# lora_breakout_36_pin.net
KiCad netlist of a schematic drawn in EAGLE
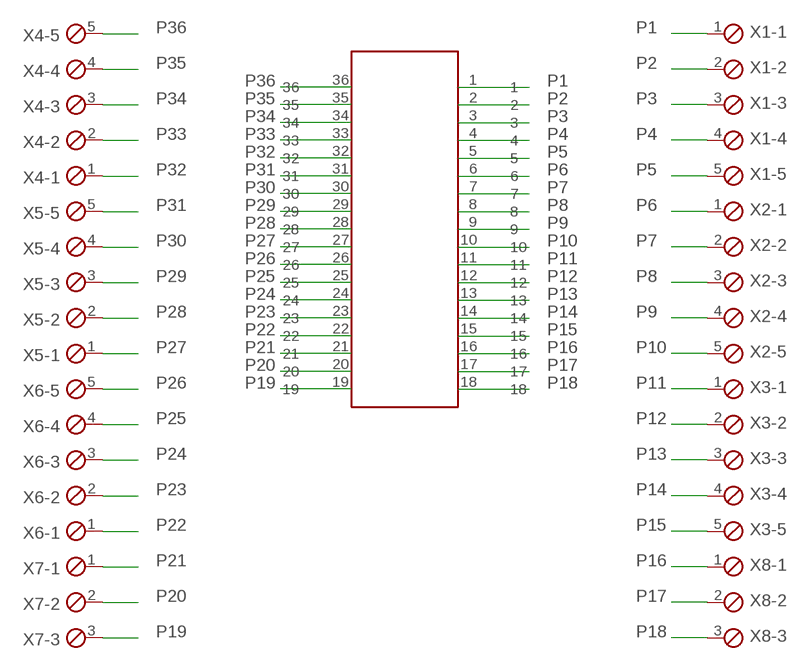
[diagram p0: schematic, sheet 1]

(export (version "E")
  (design (tool "Eeschema 10.0.6"))
  (components
    (comp (ref "U$1")
      (value "HELTECLORA")
      (footprint "eagle-import:HELTECLORA")
      (libsource (lib "eagle-import") (part "HELTECLORA"))
    )
    (comp (ref "X1")
      (value "MPT5")
      (footprint "eagle-import:5POL254")
      (libsource (lib "eagle-import") (part "MPT5"))
    )
    (comp (ref "X2")
      (value "MPT5")
      (footprint "eagle-import:5POL254")
      (libsource (lib "eagle-import") (part "MPT5"))
    )
    (comp (ref "X3")
      (value "MPT5")
      (footprint "eagle-import:5POL254")
      (libsource (lib "eagle-import") (part "MPT5"))
    )
    (comp (ref "X4")
      (value "MPT5")
      (footprint "eagle-import:5POL254")
      (libsource (lib "eagle-import") (part "MPT5"))
    )
    (comp (ref "X5")
      (value "MPT5")
      (footprint "eagle-import:5POL254")
      (libsource (lib "eagle-import") (part "MPT5"))
    )
    (comp (ref "X6")
      (value "MPT5")
      (footprint "eagle-import:5POL254")
      (libsource (lib "eagle-import") (part "MPT5"))
    )
    (comp (ref "X7")
      (value "MPT3")
      (footprint "eagle-import:3POL254")
      (libsource (lib "eagle-import") (part "MPT3"))
    )
    (comp (ref "X8")
      (value "MPT3")
      (footprint "eagle-import:3POL254")
      (libsource (lib "eagle-import") (part "MPT3"))
    )
  )
  (nets
    (net (code "1") (name "/P1") (class "Default")
      (node (ref "U$1") (pin "1") (pinfunction "1_1") (pintype "bidirectional"))
      (node (ref "X1") (pin "1") (pinfunction "1_1") (pintype "passive"))
    )
    (net (code "2") (name "/P2") (class "Default")
      (node (ref "U$1") (pin "2") (pinfunction "2_2") (pintype "bidirectional"))
      (node (ref "X1") (pin "2") (pinfunction "1_2") (pintype "passive"))
    )
    (net (code "3") (name "/P3") (class "Default")
      (node (ref "U$1") (pin "3") (pinfunction "3_3") (pintype "bidirectional"))
      (node (ref "X1") (pin "3") (pinfunction "1_3") (pintype "passive"))
    )
    (net (code "4") (name "/P4") (class "Default")
      (node (ref "U$1") (pin "4") (pinfunction "4_4") (pintype "bidirectional"))
      (node (ref "X1") (pin "4") (pinfunction "1_4") (pintype "passive"))
    )
    (net (code "5") (name "/P5") (class "Default")
      (node (ref "U$1") (pin "5") (pinfunction "5_5") (pintype "bidirectional"))
      (node (ref "X1") (pin "5") (pinfunction "1_5") (pintype "passive"))
    )
    (net (code "6") (name "/P6") (class "Default")
      (node (ref "U$1") (pin "6") (pinfunction "6_6") (pintype "bidirectional"))
      (node (ref "X2") (pin "1") (pinfunction "1_1") (pintype "passive"))
    )
    (net (code "7") (name "/P7") (class "Default")
      (node (ref "U$1") (pin "7") (pinfunction "7_7") (pintype "bidirectional"))
      (node (ref "X2") (pin "2") (pinfunction "1_2") (pintype "passive"))
    )
    (net (code "8") (name "/P8") (class "Default")
      (node (ref "U$1") (pin "8") (pinfunction "8_8") (pintype "bidirectional"))
      (node (ref "X2") (pin "3") (pinfunction "1_3") (pintype "passive"))
    )
    (net (code "9") (name "/P9") (class "Default")
      (node (ref "U$1") (pin "9") (pinfunction "9_9") (pintype "bidirectional"))
      (node (ref "X2") (pin "4") (pinfunction "1_4") (pintype "passive"))
    )
    (net (code "10") (name "/P10") (class "Default")
      (node (ref "U$1") (pin "10") (pinfunction "10_10") (pintype "bidirectional"))
      (node (ref "X2") (pin "5") (pinfunction "1_5") (pintype "passive"))
    )
    (net (code "11") (name "/P11") (class "Default")
      (node (ref "U$1") (pin "11") (pinfunction "11_11") (pintype "bidirectional"))
      (node (ref "X3") (pin "1") (pinfunction "1_1") (pintype "passive"))
    )
    (net (code "12") (name "/P12") (class "Default")
      (node (ref "U$1") (pin "12") (pinfunction "12_12") (pintype "bidirectional"))
      (node (ref "X3") (pin "2") (pinfunction "1_2") (pintype "passive"))
    )
    (net (code "13") (name "/P13") (class "Default")
      (node (ref "U$1") (pin "13") (pinfunction "13_13") (pintype "bidirectional"))
      (node (ref "X3") (pin "3") (pinfunction "1_3") (pintype "passive"))
    )
    (net (code "14") (name "/P14") (class "Default")
      (node (ref "U$1") (pin "14") (pinfunction "14_14") (pintype "bidirectional"))
      (node (ref "X3") (pin "4") (pinfunction "1_4") (pintype "passive"))
    )
    (net (code "15") (name "/P15") (class "Default")
      (node (ref "U$1") (pin "15") (pinfunction "15_15") (pintype "bidirectional"))
      (node (ref "X3") (pin "5") (pinfunction "1_5") (pintype "passive"))
    )
    (net (code "16") (name "/P16") (class "Default")
      (node (ref "U$1") (pin "16") (pinfunction "16_16") (pintype "bidirectional"))
      (node (ref "X8") (pin "1") (pinfunction "1_1") (pintype "passive"))
    )
    (net (code "17") (name "/P17") (class "Default")
      (node (ref "U$1") (pin "17") (pinfunction "17_17") (pintype "bidirectional"))
      (node (ref "X8") (pin "2") (pinfunction "1_2") (pintype "passive"))
    )
    (net (code "18") (name "/P18") (class "Default")
      (node (ref "U$1") (pin "18") (pinfunction "18_18") (pintype "bidirectional"))
      (node (ref "X8") (pin "3") (pinfunction "1_3") (pintype "passive"))
    )
    (net (code "19") (name "/P19") (class "Default")
      (node (ref "U$1") (pin "19") (pinfunction "19_19") (pintype "bidirectional"))
      (node (ref "X7") (pin "3") (pinfunction "1_3") (pintype "passive"))
    )
    (net (code "20") (name "/P20") (class "Default")
      (node (ref "U$1") (pin "20") (pinfunction "20_20") (pintype "bidirectional"))
      (node (ref "X7") (pin "2") (pinfunction "1_2") (pintype "passive"))
    )
    (net (code "21") (name "/P21") (class "Default")
      (node (ref "U$1") (pin "21") (pinfunction "21_21") (pintype "bidirectional"))
      (node (ref "X7") (pin "1") (pinfunction "1_1") (pintype "passive"))
    )
    (net (code "22") (name "/P22") (class "Default")
      (node (ref "U$1") (pin "22") (pinfunction "22_22") (pintype "bidirectional"))
      (node (ref "X6") (pin "1") (pinfunction "1_1") (pintype "passive"))
    )
    (net (code "23") (name "/P23") (class "Default")
      (node (ref "U$1") (pin "23") (pinfunction "23_23") (pintype "bidirectional"))
      (node (ref "X6") (pin "2") (pinfunction "1_2") (pintype "passive"))
    )
    (net (code "24") (name "/P24") (class "Default")
      (node (ref "U$1") (pin "24") (pinfunction "24_24") (pintype "bidirectional"))
      (node (ref "X6") (pin "3") (pinfunction "1_3") (pintype "passive"))
    )
    (net (code "25") (name "/P25") (class "Default")
      (node (ref "U$1") (pin "25") (pinfunction "25_25") (pintype "bidirectional"))
      (node (ref "X6") (pin "4") (pinfunction "1_4") (pintype "passive"))
    )
    (net (code "26") (name "/P26") (class "Default")
      (node (ref "U$1") (pin "26") (pinfunction "26_26") (pintype "bidirectional"))
      (node (ref "X6") (pin "5") (pinfunction "1_5") (pintype "passive"))
    )
    (net (code "27") (name "/P27") (class "Default")
      (node (ref "U$1") (pin "27") (pinfunction "27_27") (pintype "bidirectional"))
      (node (ref "X5") (pin "1") (pinfunction "1_1") (pintype "passive"))
    )
    (net (code "28") (name "/P28") (class "Default")
      (node (ref "U$1") (pin "28") (pinfunction "28_28") (pintype "bidirectional"))
      (node (ref "X5") (pin "2") (pinfunction "1_2") (pintype "passive"))
    )
    (net (code "29") (name "/P29") (class "Default")
      (node (ref "U$1") (pin "29") (pinfunction "29_29") (pintype "bidirectional"))
      (node (ref "X5") (pin "3") (pinfunction "1_3") (pintype "passive"))
    )
    (net (code "30") (name "/P30") (class "Default")
      (node (ref "U$1") (pin "30") (pinfunction "30_30") (pintype "bidirectional"))
      (node (ref "X5") (pin "4") (pinfunction "1_4") (pintype "passive"))
    )
    (net (code "31") (name "/P31") (class "Default")
      (node (ref "U$1") (pin "31") (pinfunction "31_31") (pintype "bidirectional"))
      (node (ref "X5") (pin "5") (pinfunction "1_5") (pintype "passive"))
    )
    (net (code "32") (name "/P32") (class "Default")
      (node (ref "U$1") (pin "32") (pinfunction "32_32") (pintype "bidirectional"))
      (node (ref "X4") (pin "1") (pinfunction "1_1") (pintype "passive"))
    )
    (net (code "33") (name "/P33") (class "Default")
      (node (ref "U$1") (pin "33") (pinfunction "33_33") (pintype "bidirectional"))
      (node (ref "X4") (pin "2") (pinfunction "1_2") (pintype "passive"))
    )
    (net (code "34") (name "/P34") (class "Default")
      (node (ref "U$1") (pin "34") (pinfunction "34_34") (pintype "bidirectional"))
      (node (ref "X4") (pin "3") (pinfunction "1_3") (pintype "passive"))
    )
    (net (code "35") (name "/P35") (class "Default")
      (node (ref "U$1") (pin "35") (pinfunction "35_35") (pintype "bidirectional"))
      (node (ref "X4") (pin "4") (pinfunction "1_4") (pintype "passive"))
    )
    (net (code "36") (name "/P36") (class "Default")
      (node (ref "U$1") (pin "36") (pinfunction "36_36") (pintype "bidirectional"))
      (node (ref "X4") (pin "5") (pinfunction "1_5") (pintype "passive"))
    )
  )
)
